# syma-wireless-charger.net
KiCad netlist of a schematic drawn in EAGLE
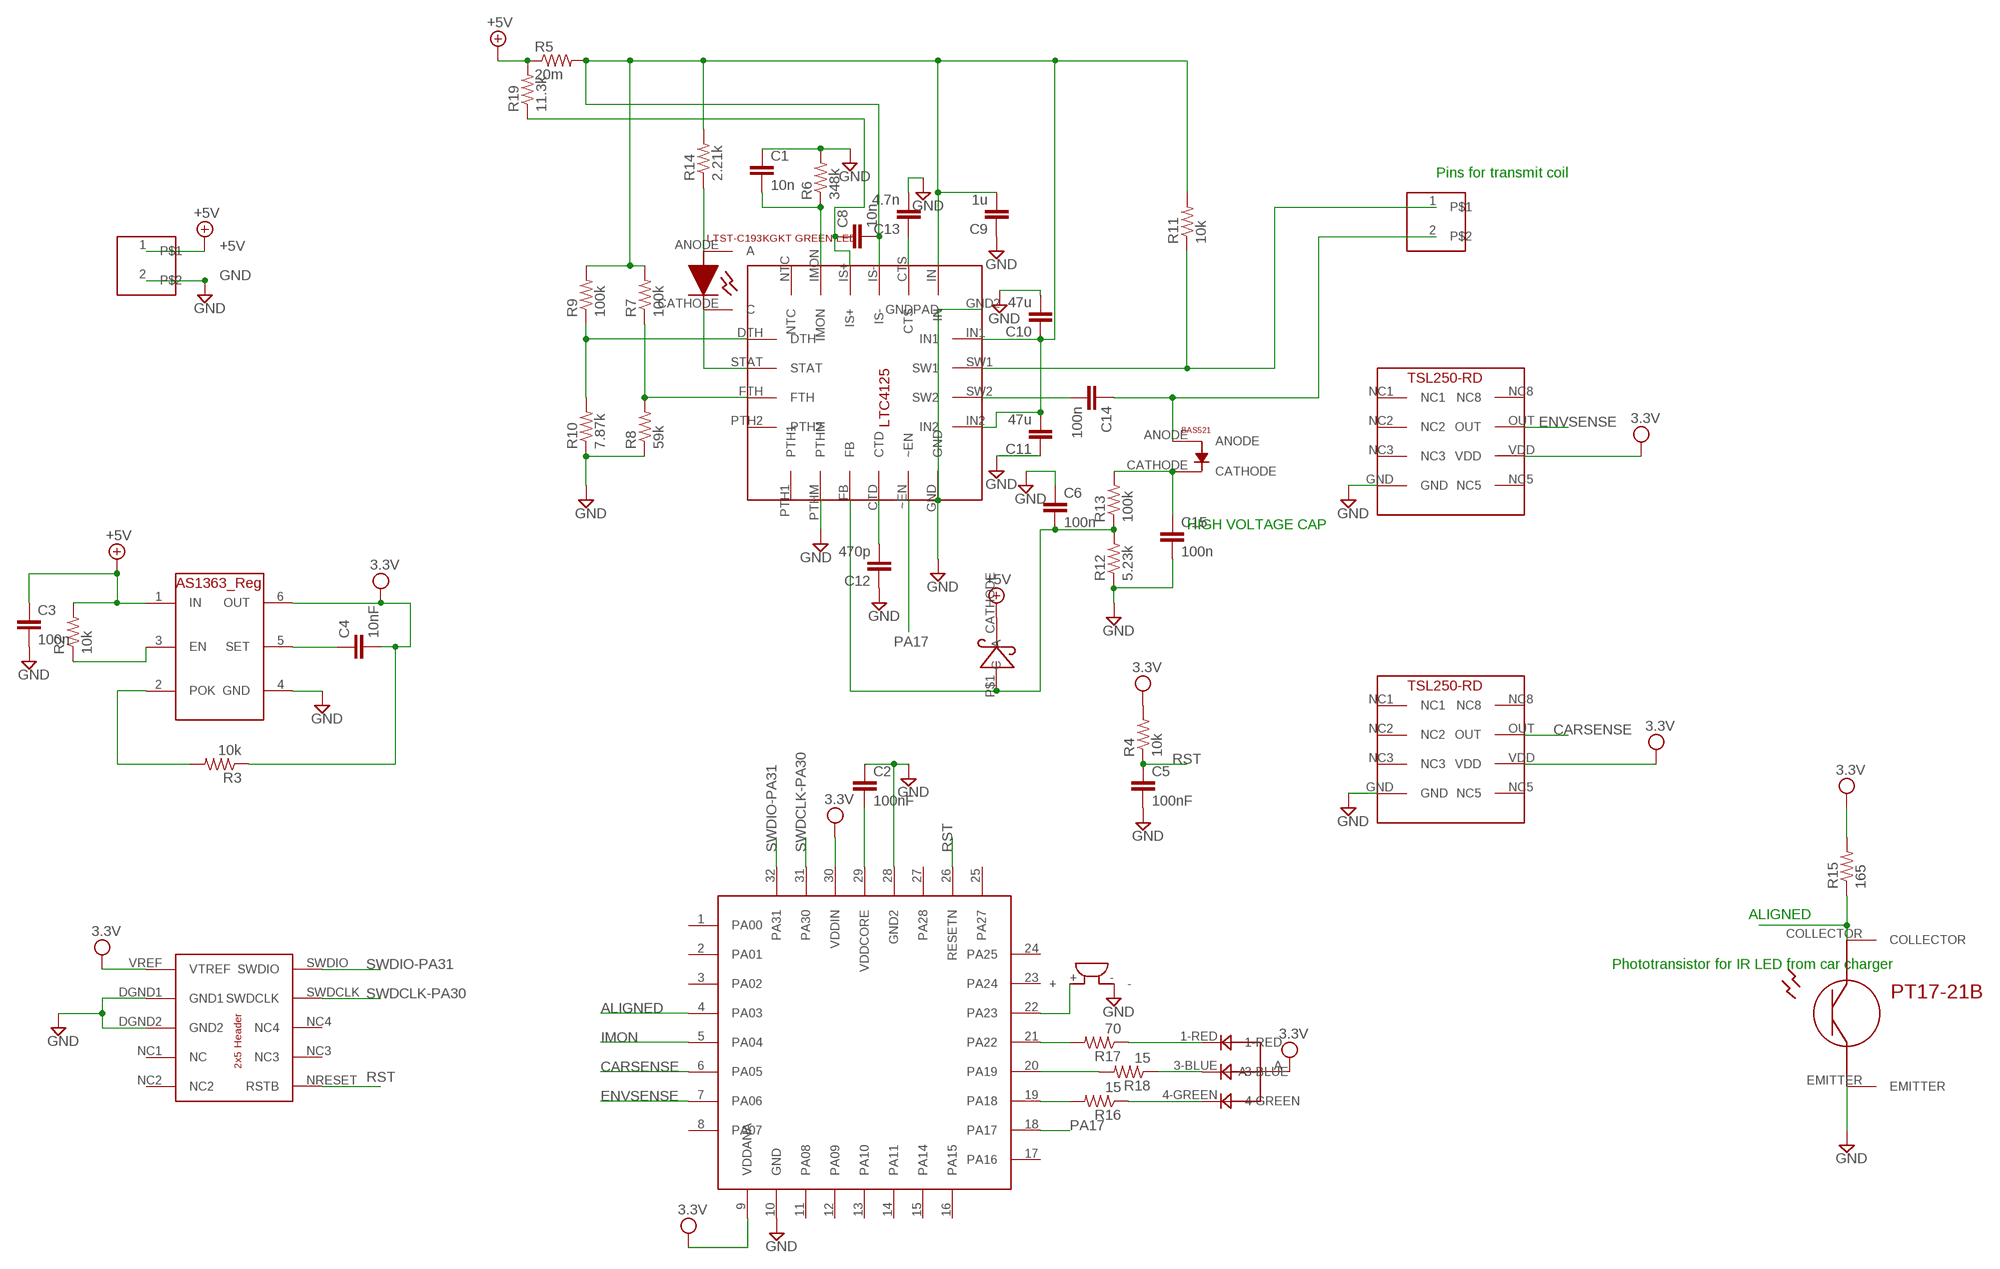
[diagram p0: schematic, sheet 1]

(export (version "E")
  (design (tool "Eeschema 10.0.6"))
  (components
    (comp (ref "C1")
      (value "10n")
      (footprint "eagle-import:C0805")
      (libsource (lib "eagle-import") (part "C-EUC0805"))
    )
    (comp (ref "C2")
      (value "100nF")
      (footprint "eagle-import:C0805K")
      (libsource (lib "eagle-import") (part "resistor_C-EUC0805K"))
    )
    (comp (ref "C3")
      (value "100n")
      (footprint "eagle-import:C0805K")
      (libsource (lib "eagle-import") (part "resistor_C-EUC0805K"))
    )
    (comp (ref "C4")
      (value "10nF")
      (footprint "eagle-import:C0805K")
      (libsource (lib "eagle-import") (part "resistor_C-EUC0805K"))
    )
    (comp (ref "C5")
      (value "100nF")
      (footprint "eagle-import:C0805K")
      (libsource (lib "eagle-import") (part "resistor_C-EUC0805K"))
    )
    (comp (ref "C6")
      (value "100n")
      (footprint "eagle-import:C0805")
      (libsource (lib "eagle-import") (part "C-EUC0805"))
    )
    (comp (ref "C8")
      (value "10n")
      (footprint "eagle-import:C0805")
      (libsource (lib "eagle-import") (part "C-EUC0805"))
    )
    (comp (ref "C9")
      (value "1u")
      (footprint "eagle-import:C0805")
      (libsource (lib "eagle-import") (part "C-EUC0805"))
    )
    (comp (ref "C10")
      (value "47u")
      (footprint "eagle-import:C0805")
      (libsource (lib "eagle-import") (part "C-EUC0805"))
    )
    (comp (ref "C11")
      (value "47u")
      (footprint "eagle-import:C0805")
      (libsource (lib "eagle-import") (part "C-EUC0805"))
    )
    (comp (ref "C12")
      (value "470p")
      (footprint "eagle-import:C0805")
      (libsource (lib "eagle-import") (part "C-EUC0805"))
    )
    (comp (ref "C13")
      (value "4.7n")
      (footprint "eagle-import:C0805")
      (libsource (lib "eagle-import") (part "C-EUC0805"))
    )
    (comp (ref "C14")
      (value "100n")
      (footprint "eagle-import:C1206")
      (libsource (lib "eagle-import") (part "C-EUC1206"))
    )
    (comp (ref "C15")
      (value "100n")
      (footprint "eagle-import:C0603")
      (libsource (lib "eagle-import") (part "resistor_C-EUC0603"))
    )
    (comp (ref "DBG1")
      (value "DEBUGHEAD")
      (footprint "eagle-import:DEBUGHEAD")
      (libsource (lib "eagle-import") (part "DEBUGHEAD"))
    )
    (comp (ref "R2")
      (value "10k")
      (footprint "eagle-import:R0805")
      (libsource (lib "eagle-import") (part "resistor_R-US_R0805"))
    )
    (comp (ref "R3")
      (value "10k")
      (footprint "eagle-import:R0805")
      (libsource (lib "eagle-import") (part "resistor_R-US_R0805"))
    )
    (comp (ref "R4")
      (value "10k")
      (footprint "eagle-import:R0805")
      (libsource (lib "eagle-import") (part "resistor_R-US_R0805"))
    )
    (comp (ref "R5")
      (value "20m")
      (footprint "eagle-import:R0805")
      (libsource (lib "eagle-import") (part "R-US_R0805"))
    )
    (comp (ref "R6")
      (value "348k")
      (footprint "eagle-import:R0805")
      (libsource (lib "eagle-import") (part "R-US_R0805"))
    )
    (comp (ref "R7")
      (value "100k")
      (footprint "eagle-import:R0805")
      (libsource (lib "eagle-import") (part "R-US_R0805"))
    )
    (comp (ref "R8")
      (value "59k")
      (footprint "eagle-import:R0805")
      (libsource (lib "eagle-import") (part "R-US_R0805"))
    )
    (comp (ref "R9")
      (value "100k")
      (footprint "eagle-import:R0805")
      (libsource (lib "eagle-import") (part "R-US_R0805"))
    )
    (comp (ref "R10")
      (value "7.87k")
      (footprint "eagle-import:R0805")
      (libsource (lib "eagle-import") (part "R-US_R0805"))
    )
    (comp (ref "R11")
      (value "10k")
      (footprint "eagle-import:R0805")
      (libsource (lib "eagle-import") (part "R-US_R0805"))
    )
    (comp (ref "R12")
      (value "5.23k")
      (footprint "eagle-import:R0805")
      (libsource (lib "eagle-import") (part "R-US_R0805"))
    )
    (comp (ref "R13")
      (value "100k")
      (footprint "eagle-import:R0805")
      (libsource (lib "eagle-import") (part "R-US_R0805"))
    )
    (comp (ref "R14")
      (value "2.21k")
      (footprint "eagle-import:R0805")
      (libsource (lib "eagle-import") (part "R-US_R0805"))
    )
    (comp (ref "R15")
      (value "165")
      (footprint "eagle-import:R0805")
      (libsource (lib "eagle-import") (part "resistor_R-US_R0805"))
    )
    (comp (ref "R16")
      (value "15")
      (footprint "eagle-import:R0805")
      (libsource (lib "eagle-import") (part "resistor_R-US_R0805"))
    )
    (comp (ref "R17")
      (value "70")
      (footprint "eagle-import:R0805")
      (libsource (lib "eagle-import") (part "resistor_R-US_R0805"))
    )
    (comp (ref "R18")
      (value "15")
      (footprint "eagle-import:R0805")
      (libsource (lib "eagle-import") (part "resistor_R-US_R0805"))
    )
    (comp (ref "R19")
      (value "11.3k")
      (footprint "eagle-import:R0805")
      (libsource (lib "eagle-import") (part "R-US_R0805"))
    )
    (comp (ref "U$1")
      (value "LTC4125")
      (footprint "eagle-import:LTC1945-QFN")
      (libsource (lib "eagle-import") (part "LTC4125"))
    )
    (comp (ref "U$2")
      (value "BAS521")
      (footprint "eagle-import:BAS521-V-DIODE")
      (libsource (lib "eagle-import") (part "BAS521"))
    )
    (comp (ref "U$3")
      (value "1X02")
      (footprint "eagle-import:1X02")
      (libsource (lib "eagle-import") (part "1X02"))
    )
    (comp (ref "U$4")
      (value "RGBLED")
      (footprint "eagle-import:RGBLED")
      (libsource (lib "eagle-import") (part "RGBLED"))
    )
    (comp (ref "U$5")
      (value "BUZZER")
      (footprint "eagle-import:BUZZER")
      (libsource (lib "eagle-import") (part "BUZZER"))
    )
    (comp (ref "U$6")
      (value "TSL250-RD")
      (footprint "eagle-import:TSL250-RD")
      (libsource (lib "eagle-import") (part "TSL250-RD"))
    )
    (comp (ref "U$7")
      (value "TSL250-RD")
      (footprint "eagle-import:TSL250-RD")
      (libsource (lib "eagle-import") (part "TSL250-RD"))
    )
    (comp (ref "U$8")
      (value "SCHTKYDIODE-523")
      (footprint "eagle-import:SOD-523")
      (libsource (lib "eagle-import") (part "SCHTKYDIODE-523"))
    )
    (comp (ref "U$9")
      (value "LTST-C193KGKT_GREEN-LED")
      (footprint "eagle-import:LTST-C193KGKT_GREEN-LED")
      (libsource (lib "eagle-import") (part "LTST-C193KGKT_GREEN-LED"))
    )
    (comp (ref "U$10")
      (value "PT17-21B_PHOTOTRANSISTOR")
      (footprint "eagle-import:PT17-21B_PHOTOTRANSISTOR")
      (libsource (lib "eagle-import") (part "PT17-21B_PHOTOTRANSISTOR"))
    )
    (comp (ref "U$11")
      (value "1X02")
      (footprint "eagle-import:1X02")
      (libsource (lib "eagle-import") (part "1X02"))
    )
    (comp (ref "U1")
      (value "SAMD21E")
      (footprint "eagle-import:TQFP32-08")
      (libsource (lib "eagle-import") (part "SAMD21E"))
    )
    (comp (ref "U2")
      (value "3.3V_AS1363")
      (footprint "eagle-import:SOT23-6")
      (libsource (lib "eagle-import") (part "3.3V_AS1363"))
    )
  )
  (nets
    (net (code "1") (name "+5V") (class "Default")
      (node (ref "C3") (pin "1") (pinfunction "1_1") (pintype "passive"))
      (node (ref "R19") (pin "2") (pinfunction "2_2") (pintype "passive"))
      (node (ref "R2") (pin "2") (pinfunction "2_2") (pintype "passive"))
      (node (ref "R5") (pin "1") (pinfunction "1_1") (pintype "passive"))
      (node (ref "U$3") (pin "1") (pinfunction "P$1_1") (pintype "bidirectional"))
      (node (ref "U$8") (pin "CATHODE") (pinfunction "C_CATHODE") (pintype "bidirectional"))
      (node (ref "U2") (pin "1") (pinfunction "IN_1") (pintype "bidirectional"))
    )
    (net (code "2") (name "/ALIGNED") (class "Default")
      (node (ref "R15") (pin "1") (pinfunction "1_1") (pintype "passive"))
      (node (ref "U$10") (pin "COLLECTOR") (pinfunction "COLLECTOR_COLLECTOR") (pintype "bidirectional"))
      (node (ref "U1") (pin "4") (pinfunction "PA03_4") (pintype "bidirectional"))
    )
    (net (code "3") (name "/CARSENSE") (class "Default")
      (node (ref "U$6") (pin "OUT") (pinfunction "OUT_OUT") (pintype "bidirectional"))
      (node (ref "U1") (pin "6") (pinfunction "PA05_6") (pintype "bidirectional"))
    )
    (net (code "4") (name "/ENVSENSE") (class "Default")
      (node (ref "U$7") (pin "OUT") (pinfunction "OUT_OUT") (pintype "bidirectional"))
      (node (ref "U1") (pin "7") (pinfunction "PA06_7") (pintype "bidirectional"))
    )
    (net (code "5") (name "/IMON") (class "Default")
      (node (ref "U1") (pin "5") (pinfunction "PA04_5") (pintype "bidirectional"))
    )
    (net (code "6") (name "/PA17") (class "Default")
      (node (ref "U$1") (pin "~EN") (pinfunction "~{EN}_~EN") (pintype "bidirectional"))
      (node (ref "U1") (pin "18") (pinfunction "PA17_18") (pintype "bidirectional"))
    )
    (net (code "7") (name "/RST") (class "Default")
      (node (ref "C5") (pin "1") (pinfunction "1_1") (pintype "passive"))
      (node (ref "DBG1") (pin "NRESET") (pinfunction "RSTB_NRESET") (pintype "bidirectional"))
      (node (ref "R4") (pin "1") (pinfunction "1_1") (pintype "passive"))
      (node (ref "U1") (pin "26") (pinfunction "RESETN_26") (pintype "bidirectional"))
    )
    (net (code "8") (name "/SWDCLK-PA30") (class "Default")
      (node (ref "DBG1") (pin "SWDCLK") (pinfunction "SWDCLK_SWDCLK") (pintype "bidirectional"))
      (node (ref "U1") (pin "31") (pinfunction "PA30_31") (pintype "bidirectional"))
    )
    (net (code "9") (name "/SWDIO-PA31") (class "Default")
      (node (ref "DBG1") (pin "SWDIO") (pinfunction "SWDIO_SWDIO") (pintype "bidirectional"))
      (node (ref "U1") (pin "32") (pinfunction "PA31_32") (pintype "bidirectional"))
    )
    (net (code "10") (name "3.3V") (class "Default")
      (node (ref "C4") (pin "2") (pinfunction "2_2") (pintype "passive"))
      (node (ref "DBG1") (pin "VREF") (pinfunction "VTREF_VREF") (pintype "bidirectional"))
      (node (ref "R15") (pin "2") (pinfunction "2_2") (pintype "passive"))
      (node (ref "R3") (pin "1") (pinfunction "1_1") (pintype "passive"))
      (node (ref "R4") (pin "2") (pinfunction "2_2") (pintype "passive"))
      (node (ref "U$4") (pin "A") (pinfunction "A_A") (pintype "bidirectional"))
      (node (ref "U$6") (pin "VDD") (pinfunction "VDD_VDD") (pintype "bidirectional"))
      (node (ref "U$7") (pin "VDD") (pinfunction "VDD_VDD") (pintype "bidirectional"))
      (node (ref "U1") (pin "30") (pinfunction "VDDIN_30") (pintype "bidirectional"))
      (node (ref "U1") (pin "9") (pinfunction "VDDANA_9") (pintype "bidirectional"))
      (node (ref "U2") (pin "6") (pinfunction "OUT_6") (pintype "bidirectional"))
    )
    (net (code "11") (name "GND") (class "Default")
      (node (ref "C1") (pin "1") (pinfunction "1_1") (pintype "passive"))
      (node (ref "C10") (pin "2") (pinfunction "2_2") (pintype "passive"))
      (node (ref "C11") (pin "1") (pinfunction "1_1") (pintype "passive"))
      (node (ref "C12") (pin "1") (pinfunction "1_1") (pintype "passive"))
      (node (ref "C13") (pin "2") (pinfunction "2_2") (pintype "passive"))
      (node (ref "C15") (pin "2") (pinfunction "2_2") (pintype "passive"))
      (node (ref "C2") (pin "1") (pinfunction "1_1") (pintype "passive"))
      (node (ref "C3") (pin "2") (pinfunction "2_2") (pintype "passive"))
      (node (ref "C5") (pin "2") (pinfunction "2_2") (pintype "passive"))
      (node (ref "C6") (pin "1") (pinfunction "1_1") (pintype "passive"))
      (node (ref "C9") (pin "1") (pinfunction "1_1") (pintype "passive"))
      (node (ref "DBG1") (pin "DGND1") (pinfunction "GND1_DGND1") (pintype "bidirectional"))
      (node (ref "DBG1") (pin "DGND2") (pinfunction "GND2_DGND2") (pintype "bidirectional"))
      (node (ref "R10") (pin "1") (pinfunction "1_1") (pintype "passive"))
      (node (ref "R12") (pin "1") (pinfunction "1_1") (pintype "passive"))
      (node (ref "R6") (pin "2") (pinfunction "2_2") (pintype "passive"))
      (node (ref "R8") (pin "1") (pinfunction "1_1") (pintype "passive"))
      (node (ref "U$1") (pin "GND") (pinfunction "GND_GND") (pintype "bidirectional"))
      (node (ref "U$1") (pin "GND2") (pinfunction "GNDPAD_GND2") (pintype "bidirectional"))
      (node (ref "U$1") (pin "PTHM") (pinfunction "PTHM_PTHM") (pintype "bidirectional"))
      (node (ref "U$10") (pin "EMITTER") (pinfunction "EMITTER_EMITTER") (pintype "bidirectional"))
      (node (ref "U$3") (pin "2") (pinfunction "P$2_2") (pintype "bidirectional"))
      (node (ref "U$5") (pin "-") (pinfunction "-_-") (pintype "bidirectional"))
      (node (ref "U$6") (pin "GND") (pinfunction "GND_GND") (pintype "bidirectional"))
      (node (ref "U$7") (pin "GND") (pinfunction "GND_GND") (pintype "bidirectional"))
      (node (ref "U1") (pin "10") (pinfunction "GND_10") (pintype "bidirectional"))
      (node (ref "U1") (pin "28") (pinfunction "GND2_28") (pintype "bidirectional"))
      (node (ref "U2") (pin "4") (pinfunction "GND_4") (pintype "bidirectional"))
    )
    (net (code "12") (name "Net-(C1-Pad2)") (class "Default")
      (node (ref "C1") (pin "2") (pinfunction "2_2") (pintype "passive"))
      (node (ref "R6") (pin "1") (pinfunction "1_1") (pintype "passive"))
      (node (ref "U$1") (pin "IMON") (pinfunction "IMON_IMON") (pintype "bidirectional"))
    )
    (net (code "13") (name "Net-(C8-Pad1)") (class "Default")
      (node (ref "C8") (pin "1") (pinfunction "1_1") (pintype "passive"))
      (node (ref "R19") (pin "1") (pinfunction "1_1") (pintype "passive"))
      (node (ref "U$1") (pin "IS+") (pinfunction "IS+_IS+") (pintype "bidirectional"))
    )
    (net (code "14") (name "Net-(C10-Pad1)") (class "Default")
      (node (ref "C10") (pin "1") (pinfunction "1_1") (pintype "passive"))
      (node (ref "C11") (pin "2") (pinfunction "2_2") (pintype "passive"))
      (node (ref "C8") (pin "2") (pinfunction "2_2") (pintype "passive"))
      (node (ref "C9") (pin "2") (pinfunction "2_2") (pintype "passive"))
      (node (ref "R11") (pin "2") (pinfunction "2_2") (pintype "passive"))
      (node (ref "R14") (pin "2") (pinfunction "2_2") (pintype "passive"))
      (node (ref "R5") (pin "2") (pinfunction "2_2") (pintype "passive"))
      (node (ref "R7") (pin "2") (pinfunction "2_2") (pintype "passive"))
      (node (ref "R9") (pin "2") (pinfunction "2_2") (pintype "passive"))
      (node (ref "U$1") (pin "IN") (pinfunction "IN_IN") (pintype "bidirectional"))
      (node (ref "U$1") (pin "IN1") (pinfunction "IN1_IN1") (pintype "bidirectional"))
      (node (ref "U$1") (pin "IN2") (pinfunction "IN2_IN2") (pintype "bidirectional"))
      (node (ref "U$1") (pin "IS-") (pinfunction "IS-_IS-") (pintype "bidirectional"))
    )
    (net (code "15") (name "Net-(C12-Pad2)") (class "Default")
      (node (ref "C12") (pin "2") (pinfunction "2_2") (pintype "passive"))
      (node (ref "U$1") (pin "CTD") (pinfunction "CTD_CTD") (pintype "bidirectional"))
    )
    (net (code "16") (name "Net-(C13-Pad1)") (class "Default")
      (node (ref "C13") (pin "1") (pinfunction "1_1") (pintype "passive"))
      (node (ref "U$1") (pin "CTS") (pinfunction "CTS_CTS") (pintype "bidirectional"))
    )
    (net (code "17") (name "Net-(C14-Pad2)") (class "Default")
      (node (ref "C14") (pin "2") (pinfunction "2_2") (pintype "passive"))
      (node (ref "U$1") (pin "SW2") (pinfunction "SW2_SW2") (pintype "bidirectional"))
    )
    (net (code "18") (name "Net-(C15-Pad1)") (class "Default")
      (node (ref "C15") (pin "1") (pinfunction "1_1") (pintype "passive"))
      (node (ref "R13") (pin "2") (pinfunction "2_2") (pintype "passive"))
      (node (ref "U$2") (pin "CATHODE") (pinfunction "CATHODE_CATHODE") (pintype "bidirectional"))
    )
    (net (code "19") (name "Net-(R7-Pad1)") (class "Default")
      (node (ref "R7") (pin "1") (pinfunction "1_1") (pintype "passive"))
      (node (ref "R8") (pin "2") (pinfunction "2_2") (pintype "passive"))
      (node (ref "U$1") (pin "FTH") (pinfunction "FTH_FTH") (pintype "bidirectional"))
    )
    (net (code "20") (name "Net-(R10-Pad2)") (class "Default")
      (node (ref "R10") (pin "2") (pinfunction "2_2") (pintype "passive"))
      (node (ref "R9") (pin "1") (pinfunction "1_1") (pintype "passive"))
      (node (ref "U$1") (pin "DTH") (pinfunction "DTH_DTH") (pintype "bidirectional"))
    )
    (net (code "21") (name "Net-(R16-Pad1)") (class "Default")
      (node (ref "R16") (pin "1") (pinfunction "1_1") (pintype "passive"))
      (node (ref "U$4") (pin "4-GREEN") (pinfunction "4-GREEN_4-GREEN") (pintype "bidirectional"))
    )
    (net (code "22") (name "Net-(R17-Pad1)") (class "Default")
      (node (ref "R17") (pin "1") (pinfunction "1_1") (pintype "passive"))
      (node (ref "U$4") (pin "1-RED") (pinfunction "1-RED_1-RED") (pintype "bidirectional"))
    )
    (net (code "23") (name "Net-(R18-Pad1)") (class "Default")
      (node (ref "R18") (pin "1") (pinfunction "1_1") (pintype "passive"))
      (node (ref "U$4") (pin "3-BLUE") (pinfunction "3-BLUE_3-BLUE") (pintype "bidirectional"))
    )
    (net (code "24") (name "Net-(U$8-A)") (class "Default")
      (node (ref "C6") (pin "2") (pinfunction "2_2") (pintype "passive"))
      (node (ref "R12") (pin "2") (pinfunction "2_2") (pintype "passive"))
      (node (ref "R13") (pin "1") (pinfunction "1_1") (pintype "passive"))
      (node (ref "U$1") (pin "FB") (pinfunction "FB_FB") (pintype "bidirectional"))
      (node (ref "U$8") (pin "P$1") (pinfunction "A_P$1") (pintype "bidirectional"))
    )
    (net (code "25") (name "Net-(U$9-A)") (class "Default")
      (node (ref "R14") (pin "1") (pinfunction "1_1") (pintype "passive"))
      (node (ref "U$9") (pin "ANODE") (pinfunction "A_ANODE") (pintype "bidirectional"))
    )
    (net (code "26") (name "Net-(U$9-C)") (class "Default")
      (node (ref "U$1") (pin "STAT") (pinfunction "STAT_STAT") (pintype "bidirectional"))
      (node (ref "U$9") (pin "CATHODE") (pinfunction "C_CATHODE") (pintype "bidirectional"))
    )
    (net (code "27") (name "Net-(U$11-P$1)") (class "Default")
      (node (ref "R11") (pin "1") (pinfunction "1_1") (pintype "passive"))
      (node (ref "U$1") (pin "SW1") (pinfunction "SW1_SW1") (pintype "bidirectional"))
      (node (ref "U$11") (pin "1") (pinfunction "P$1_1") (pintype "bidirectional"))
    )
    (net (code "28") (name "Net-(U$11-P$2)") (class "Default")
      (node (ref "C14") (pin "1") (pinfunction "1_1") (pintype "passive"))
      (node (ref "U$11") (pin "2") (pinfunction "P$2_2") (pintype "bidirectional"))
      (node (ref "U$2") (pin "ANODE") (pinfunction "ANODE_ANODE") (pintype "bidirectional"))
    )
    (net (code "29") (name "Net-(U1-PA18)") (class "Default")
      (node (ref "R16") (pin "2") (pinfunction "2_2") (pintype "passive"))
      (node (ref "U1") (pin "19") (pinfunction "PA18_19") (pintype "bidirectional"))
    )
    (net (code "30") (name "Net-(U1-PA19)") (class "Default")
      (node (ref "R18") (pin "2") (pinfunction "2_2") (pintype "passive"))
      (node (ref "U1") (pin "20") (pinfunction "PA19_20") (pintype "bidirectional"))
    )
    (net (code "31") (name "Net-(U1-PA22)") (class "Default")
      (node (ref "R17") (pin "2") (pinfunction "2_2") (pintype "passive"))
      (node (ref "U1") (pin "21") (pinfunction "PA22_21") (pintype "bidirectional"))
    )
    (net (code "32") (name "Net-(U1-PA23)") (class "Default")
      (node (ref "U$5") (pin "+") (pinfunction "+_+") (pintype "bidirectional"))
      (node (ref "U1") (pin "22") (pinfunction "PA23_22") (pintype "bidirectional"))
    )
    (net (code "33") (name "Net-(U1-VDDCORE)") (class "Default")
      (node (ref "C2") (pin "2") (pinfunction "2_2") (pintype "passive"))
      (node (ref "U1") (pin "29") (pinfunction "VDDCORE_29") (pintype "bidirectional"))
    )
    (net (code "34") (name "Net-(U2-EN)") (class "Default")
      (node (ref "R2") (pin "1") (pinfunction "1_1") (pintype "passive"))
      (node (ref "U2") (pin "3") (pinfunction "EN_3") (pintype "bidirectional"))
    )
    (net (code "35") (name "Net-(U2-POK)") (class "Default")
      (node (ref "R3") (pin "2") (pinfunction "2_2") (pintype "passive"))
      (node (ref "U2") (pin "2") (pinfunction "POK_2") (pintype "bidirectional"))
    )
    (net (code "36") (name "Net-(U2-SET)") (class "Default")
      (node (ref "C4") (pin "1") (pinfunction "1_1") (pintype "passive"))
      (node (ref "U2") (pin "5") (pinfunction "SET_5") (pintype "bidirectional"))
    )
    (net (code "37") (name "unconnected-(DBG1-NC-PadNC1)") (class "Default")
      (node (ref "DBG1") (pin "NC1") (pinfunction "NC_NC1") (pintype "bidirectional"))
    )
    (net (code "38") (name "unconnected-(DBG1-PadNC2)") (class "Default")
      (node (ref "DBG1") (pin "NC2") (pinfunction "NC2_NC2") (pintype "bidirectional"))
    )
    (net (code "39") (name "unconnected-(DBG1-PadNC3)") (class "Default")
      (node (ref "DBG1") (pin "NC3") (pinfunction "NC3_NC3") (pintype "bidirectional"))
    )
    (net (code "40") (name "unconnected-(DBG1-PadNC4)") (class "Default")
      (node (ref "DBG1") (pin "NC4") (pinfunction "NC4_NC4") (pintype "bidirectional"))
    )
    (net (code "41") (name "unconnected-(U$1-PadNTC)") (class "Default")
      (node (ref "U$1") (pin "NTC") (pinfunction "NTC_NTC") (pintype "bidirectional"))
    )
    (net (code "42") (name "unconnected-(U$1-PadPTH1)") (class "Default")
      (node (ref "U$1") (pin "PTH1") (pinfunction "PTH1_PTH1") (pintype "bidirectional"))
    )
    (net (code "43") (name "unconnected-(U$1-PadPTH2)") (class "Default")
      (node (ref "U$1") (pin "PTH2") (pinfunction "PTH2_PTH2") (pintype "bidirectional"))
    )
    (net (code "44") (name "unconnected-(U$6-PadNC1)") (class "Default")
      (node (ref "U$6") (pin "NC1") (pinfunction "NC1_NC1") (pintype "bidirectional"))
    )
    (net (code "45") (name "unconnected-(U$6-PadNC2)") (class "Default")
      (node (ref "U$6") (pin "NC2") (pinfunction "NC2_NC2") (pintype "bidirectional"))
    )
    (net (code "46") (name "unconnected-(U$6-PadNC3)") (class "Default")
      (node (ref "U$6") (pin "NC3") (pinfunction "NC3_NC3") (pintype "bidirectional"))
    )
    (net (code "47") (name "unconnected-(U$6-PadNC5)") (class "Default")
      (node (ref "U$6") (pin "NC5") (pinfunction "NC5_NC5") (pintype "bidirectional"))
    )
    (net (code "48") (name "unconnected-(U$6-PadNC8)") (class "Default")
      (node (ref "U$6") (pin "NC8") (pinfunction "NC8_NC8") (pintype "bidirectional"))
    )
    (net (code "49") (name "unconnected-(U$7-PadNC1)") (class "Default")
      (node (ref "U$7") (pin "NC1") (pinfunction "NC1_NC1") (pintype "bidirectional"))
    )
    (net (code "50") (name "unconnected-(U$7-PadNC2)") (class "Default")
      (node (ref "U$7") (pin "NC2") (pinfunction "NC2_NC2") (pintype "bidirectional"))
    )
    (net (code "51") (name "unconnected-(U$7-PadNC3)") (class "Default")
      (node (ref "U$7") (pin "NC3") (pinfunction "NC3_NC3") (pintype "bidirectional"))
    )
    (net (code "52") (name "unconnected-(U$7-PadNC5)") (class "Default")
      (node (ref "U$7") (pin "NC5") (pinfunction "NC5_NC5") (pintype "bidirectional"))
    )
    (net (code "53") (name "unconnected-(U$7-PadNC8)") (class "Default")
      (node (ref "U$7") (pin "NC8") (pinfunction "NC8_NC8") (pintype "bidirectional"))
    )
    (net (code "54") (name "unconnected-(U1-PA00-Pad1)") (class "Default")
      (node (ref "U1") (pin "1") (pinfunction "PA00_1") (pintype "bidirectional"))
    )
    (net (code "55") (name "unconnected-(U1-PA01-Pad2)") (class "Default")
      (node (ref "U1") (pin "2") (pinfunction "PA01_2") (pintype "bidirectional"))
    )
    (net (code "56") (name "unconnected-(U1-PA02-Pad3)") (class "Default")
      (node (ref "U1") (pin "3") (pinfunction "PA02_3") (pintype "bidirectional"))
    )
    (net (code "57") (name "unconnected-(U1-PA07-Pad8)") (class "Default")
      (node (ref "U1") (pin "8") (pinfunction "PA07_8") (pintype "bidirectional"))
    )
    (net (code "58") (name "unconnected-(U1-PA08-Pad11)") (class "Default")
      (node (ref "U1") (pin "11") (pinfunction "PA08_11") (pintype "bidirectional"))
    )
    (net (code "59") (name "unconnected-(U1-PA09-Pad12)") (class "Default")
      (node (ref "U1") (pin "12") (pinfunction "PA09_12") (pintype "bidirectional"))
    )
    (net (code "60") (name "unconnected-(U1-PA10-Pad13)") (class "Default")
      (node (ref "U1") (pin "13") (pinfunction "PA10_13") (pintype "bidirectional"))
    )
    (net (code "61") (name "unconnected-(U1-PA11-Pad14)") (class "Default")
      (node (ref "U1") (pin "14") (pinfunction "PA11_14") (pintype "bidirectional"))
    )
    (net (code "62") (name "unconnected-(U1-PA14-Pad15)") (class "Default")
      (node (ref "U1") (pin "15") (pinfunction "PA14_15") (pintype "bidirectional"))
    )
    (net (code "63") (name "unconnected-(U1-PA15-Pad16)") (class "Default")
      (node (ref "U1") (pin "16") (pinfunction "PA15_16") (pintype "bidirectional"))
    )
    (net (code "64") (name "unconnected-(U1-PA16-Pad17)") (class "Default")
      (node (ref "U1") (pin "17") (pinfunction "PA16_17") (pintype "bidirectional"))
    )
    (net (code "65") (name "unconnected-(U1-PA24-Pad23)") (class "Default")
      (node (ref "U1") (pin "23") (pinfunction "PA24_23") (pintype "bidirectional"))
    )
    (net (code "66") (name "unconnected-(U1-PA25-Pad24)") (class "Default")
      (node (ref "U1") (pin "24") (pinfunction "PA25_24") (pintype "bidirectional"))
    )
    (net (code "67") (name "unconnected-(U1-PA27-Pad25)") (class "Default")
      (node (ref "U1") (pin "25") (pinfunction "PA27_25") (pintype "bidirectional"))
    )
    (net (code "68") (name "unconnected-(U1-PA28-Pad27)") (class "Default")
      (node (ref "U1") (pin "27") (pinfunction "PA28_27") (pintype "bidirectional"))
    )
  )
)
